# Nusbio1_0_WaveShare_WithLed_SeedStudio.net
KiCad netlist of a schematic drawn in EAGLE
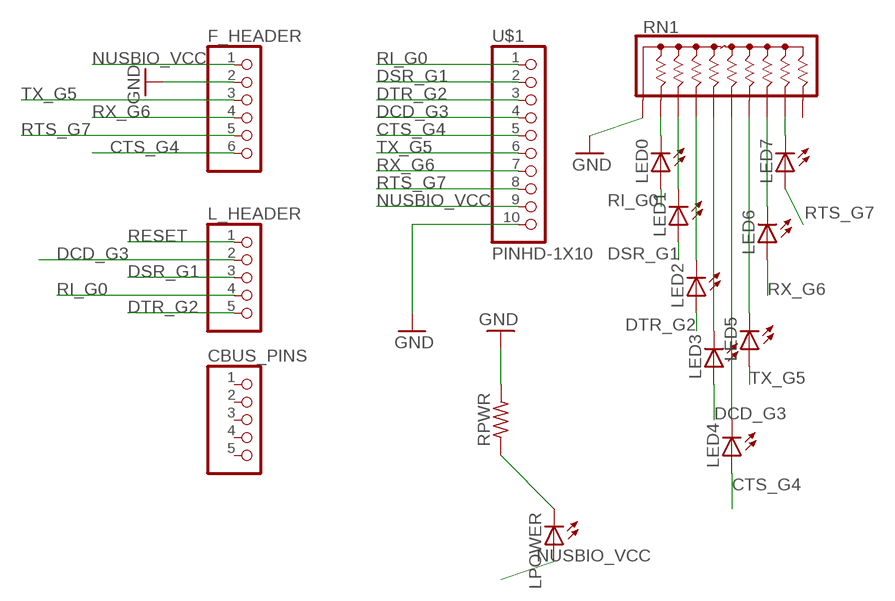
[diagram p0: schematic, sheet 1]

(export (version "E")
  (design (tool "Eeschema 10.0.6"))
  (components
    (comp (ref "CBUS_PINS")
      (value "PINHD-1X5")
      (footprint "eagle-import:1X05")
      (libsource (lib "eagle-import") (part "PINHD-1X5"))
    )
    (comp (ref "F_HEADER")
      (value "PINHD-1X6")
      (footprint "eagle-import:1X06")
      (libsource (lib "eagle-import") (part "PINHD-1X6"))
    )
    (comp (ref "LED0")
      (value "LEDSMT1206")
      (footprint "eagle-import:1206")
      (libsource (lib "eagle-import") (part "LEDSMT1206"))
    )
    (comp (ref "LED1")
      (value "LEDSMT1206")
      (footprint "eagle-import:1206")
      (libsource (lib "eagle-import") (part "LEDSMT1206"))
    )
    (comp (ref "LED2")
      (value "LEDSMT1206")
      (footprint "eagle-import:1206")
      (libsource (lib "eagle-import") (part "LEDSMT1206"))
    )
    (comp (ref "LED3")
      (value "LEDSMT1206")
      (footprint "eagle-import:1206")
      (libsource (lib "eagle-import") (part "LEDSMT1206"))
    )
    (comp (ref "LED4")
      (value "LEDSMT1206")
      (footprint "eagle-import:1206")
      (libsource (lib "eagle-import") (part "LEDSMT1206"))
    )
    (comp (ref "LED5")
      (value "LEDSMT1206")
      (footprint "eagle-import:1206")
      (libsource (lib "eagle-import") (part "LEDSMT1206"))
    )
    (comp (ref "LED6")
      (value "LEDSMT1206")
      (footprint "eagle-import:1206")
      (libsource (lib "eagle-import") (part "LEDSMT1206"))
    )
    (comp (ref "LED7")
      (value "LEDSMT1206")
      (footprint "eagle-import:1206")
      (libsource (lib "eagle-import") (part "LEDSMT1206"))
    )
    (comp (ref "LPOWER")
      (value "LEDSMT1206")
      (footprint "eagle-import:1206")
      (libsource (lib "eagle-import") (part "LEDSMT1206"))
    )
    (comp (ref "L_HEADER")
      (value "PINHD-1X5")
      (footprint "eagle-import:1X05")
      (libsource (lib "eagle-import") (part "PINHD-1X5"))
    )
    (comp (ref "RN1")
      (value "4610X")
      (footprint "eagle-import:SIP10")
      (libsource (lib "eagle-import") (part "4610X"))
    )
    (comp (ref "RPWR")
      (value "R-US_R1206")
      (footprint "eagle-import:R1206")
      (libsource (lib "eagle-import") (part "R-US_R1206"))
    )
    (comp (ref "U$1")
      (value "PINHD-1X10")
      (footprint "eagle-import:1X10-BIG")
      (libsource (lib "eagle-import") (part "PINHD-1X10"))
    )
  )
  (nets
    (net (code "1") (name "/CTS_G4") (class "Default")
      (node (ref "F_HEADER") (pin "6") (pinfunction "6_6") (pintype "passive"))
      (node (ref "LED4") (pin "A") (pinfunction "A_A") (pintype "passive"))
      (node (ref "U$1") (pin "5") (pinfunction "5_5") (pintype "passive"))
    )
    (net (code "2") (name "/DCD_G3") (class "Default")
      (node (ref "LED3") (pin "A") (pinfunction "A_A") (pintype "passive"))
      (node (ref "L_HEADER") (pin "2") (pinfunction "2_2") (pintype "passive"))
      (node (ref "U$1") (pin "4") (pinfunction "4_4") (pintype "passive"))
    )
    (net (code "3") (name "/DSR_G1") (class "Default")
      (node (ref "LED1") (pin "A") (pinfunction "A_A") (pintype "passive"))
      (node (ref "L_HEADER") (pin "3") (pinfunction "3_3") (pintype "passive"))
      (node (ref "U$1") (pin "2") (pinfunction "2_2") (pintype "passive"))
    )
    (net (code "4") (name "/DTR_G2") (class "Default")
      (node (ref "LED2") (pin "A") (pinfunction "A_A") (pintype "passive"))
      (node (ref "L_HEADER") (pin "5") (pinfunction "5_5") (pintype "passive"))
      (node (ref "U$1") (pin "3") (pinfunction "3_3") (pintype "passive"))
    )
    (net (code "5") (name "/NUSBIO_VCC") (class "Default")
      (node (ref "F_HEADER") (pin "1") (pinfunction "1_1") (pintype "passive"))
      (node (ref "LPOWER") (pin "A") (pinfunction "A_A") (pintype "passive"))
      (node (ref "U$1") (pin "9") (pinfunction "9_9") (pintype "passive"))
    )
    (net (code "6") (name "/RESET") (class "Default")
      (node (ref "L_HEADER") (pin "1") (pinfunction "1_1") (pintype "passive"))
    )
    (net (code "7") (name "/RI_G0") (class "Default")
      (node (ref "LED0") (pin "A") (pinfunction "A_A") (pintype "passive"))
      (node (ref "L_HEADER") (pin "4") (pinfunction "4_4") (pintype "passive"))
      (node (ref "U$1") (pin "1") (pinfunction "1_1") (pintype "passive"))
    )
    (net (code "8") (name "/RTS_G7") (class "Default")
      (node (ref "F_HEADER") (pin "5") (pinfunction "5_5") (pintype "passive"))
      (node (ref "LED7") (pin "A") (pinfunction "A_A") (pintype "passive"))
      (node (ref "U$1") (pin "8") (pinfunction "8_8") (pintype "passive"))
    )
    (net (code "9") (name "/RX_G6") (class "Default")
      (node (ref "F_HEADER") (pin "4") (pinfunction "4_4") (pintype "passive"))
      (node (ref "LED6") (pin "A") (pinfunction "A_A") (pintype "passive"))
      (node (ref "U$1") (pin "7") (pinfunction "7_7") (pintype "passive"))
    )
    (net (code "10") (name "/TX_G5") (class "Default")
      (node (ref "F_HEADER") (pin "3") (pinfunction "3_3") (pintype "passive"))
      (node (ref "LED5") (pin "A") (pinfunction "A_A") (pintype "passive"))
      (node (ref "U$1") (pin "6") (pinfunction "6_6") (pintype "passive"))
    )
    (net (code "11") (name "GND") (class "Default")
      (node (ref "F_HEADER") (pin "2") (pinfunction "2_2") (pintype "passive"))
      (node (ref "RN1") (pin "1") (pinfunction "1_1") (pintype "passive"))
      (node (ref "RPWR") (pin "2") (pinfunction "2_2") (pintype "passive"))
      (node (ref "U$1") (pin "10") (pinfunction "10_10") (pintype "passive"))
    )
    (net (code "12") (name "Net-(LED0-PadC)") (class "Default")
      (node (ref "LED0") (pin "C") (pinfunction "C_C") (pintype "passive"))
      (node (ref "RN1") (pin "2") (pinfunction "2_2") (pintype "passive"))
    )
    (net (code "13") (name "Net-(LED1-PadC)") (class "Default")
      (node (ref "LED1") (pin "C") (pinfunction "C_C") (pintype "passive"))
      (node (ref "RN1") (pin "3") (pinfunction "3_3") (pintype "passive"))
    )
    (net (code "14") (name "Net-(LED2-PadC)") (class "Default")
      (node (ref "LED2") (pin "C") (pinfunction "C_C") (pintype "passive"))
      (node (ref "RN1") (pin "4") (pinfunction "4_4") (pintype "passive"))
    )
    (net (code "15") (name "Net-(LED3-PadC)") (class "Default")
      (node (ref "LED3") (pin "C") (pinfunction "C_C") (pintype "passive"))
      (node (ref "RN1") (pin "5") (pinfunction "5_5") (pintype "passive"))
    )
    (net (code "16") (name "Net-(LED4-PadC)") (class "Default")
      (node (ref "LED4") (pin "C") (pinfunction "C_C") (pintype "passive"))
      (node (ref "RN1") (pin "6") (pinfunction "6_6") (pintype "passive"))
    )
    (net (code "17") (name "Net-(LED5-PadC)") (class "Default")
      (node (ref "LED5") (pin "C") (pinfunction "C_C") (pintype "passive"))
      (node (ref "RN1") (pin "7") (pinfunction "7_7") (pintype "passive"))
    )
    (net (code "18") (name "Net-(LED6-PadC)") (class "Default")
      (node (ref "LED6") (pin "C") (pinfunction "C_C") (pintype "passive"))
      (node (ref "RN1") (pin "8") (pinfunction "8_8") (pintype "passive"))
    )
    (net (code "19") (name "Net-(LED7-PadC)") (class "Default")
      (node (ref "LED7") (pin "C") (pinfunction "C_C") (pintype "passive"))
      (node (ref "RN1") (pin "9") (pinfunction "9_9") (pintype "passive"))
    )
    (net (code "20") (name "Net-(LPOWER-PadC)") (class "Default")
      (node (ref "LPOWER") (pin "C") (pinfunction "C_C") (pintype "passive"))
      (node (ref "RPWR") (pin "1") (pinfunction "1_1") (pintype "passive"))
    )
    (net (code "21") (name "unconnected-(CBUS_PINS-Pad1)") (class "Default")
      (node (ref "CBUS_PINS") (pin "1") (pinfunction "1_1") (pintype "passive"))
    )
    (net (code "22") (name "unconnected-(CBUS_PINS-Pad2)") (class "Default")
      (node (ref "CBUS_PINS") (pin "2") (pinfunction "2_2") (pintype "passive"))
    )
    (net (code "23") (name "unconnected-(CBUS_PINS-Pad3)") (class "Default")
      (node (ref "CBUS_PINS") (pin "3") (pinfunction "3_3") (pintype "passive"))
    )
    (net (code "24") (name "unconnected-(CBUS_PINS-Pad4)") (class "Default")
      (node (ref "CBUS_PINS") (pin "4") (pinfunction "4_4") (pintype "passive"))
    )
    (net (code "25") (name "unconnected-(CBUS_PINS-Pad5)") (class "Default")
      (node (ref "CBUS_PINS") (pin "5") (pinfunction "5_5") (pintype "passive"))
    )
    (net (code "26") (name "unconnected-(RN1-Pad10)") (class "Default")
      (node (ref "RN1") (pin "10") (pinfunction "10_10") (pintype "passive"))
    )
  )
)
